# Power.net
KiCad netlist of a schematic drawn in Altium Designer
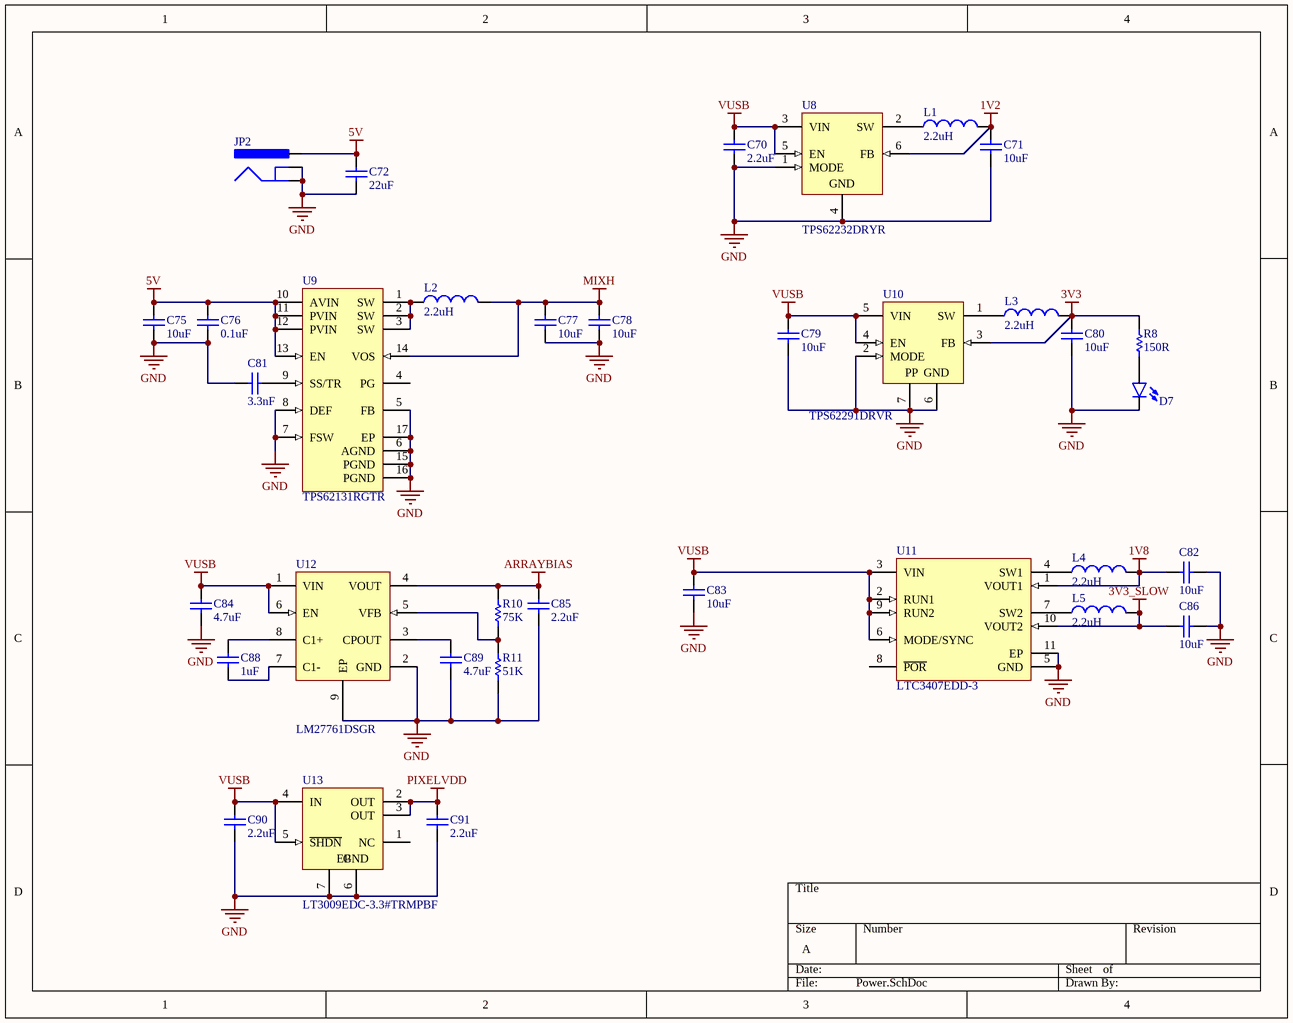
[diagram p0: Power.SchDoc]

(export (version "E")
  (design (tool "Eeschema 10.0.6"))
  (components
    (comp (ref "C70")
      (value "2.2uF")
      (footprint "C0402[1005X55]")
      (description "2.2uF 6.3V 20% 0402 (1005 Metric)")
      (fields (field (name "PARTNUMBER") "GRM155R60J225ME15D") (field (name "MANUFACTURER") "Murata"))
      (libsource (lib "Capacitors") (part "CAP_2.2uF_6.3V_0402_20%"))
    )
    (comp (ref "C71")
      (value "10uF")
      (footprint "C0402[1005X55]")
      (description "10uF 6.3V 20% 0402 (1005 Metric)")
      (fields (field (name "PARTNUMBER") "GRM155R60J106ME44D") (field (name "MANUFACTURER") "Murata"))
      (libsource (lib "Capacitors") (part "CAP_10uF_6.3V_0402_20%"))
    )
    (comp (ref "C72")
      (value "22uF")
      (footprint "C0603[1608X92]")
      (description "22uF 6.3V 10% 0603 (1608 Metric)")
      (fields (field (name "PARTNUMBER") "GRT188R60J226ME13D") (field (name "MANUFACTURER") "Murata"))
      (libsource (lib "Capacitors") (part "CAP_22uF_6.3V_0603_10%"))
    )
    (comp (ref "C75")
      (value "10uF")
      (footprint "C0402[1005X55]")
      (description "10uF 6.3V 20% 0402 (1005 Metric)")
      (fields (field (name "PARTNUMBER") "GRM155R60J106ME44D") (field (name "MANUFACTURER") "Murata"))
      (libsource (lib "Capacitors") (part "CAP_10uF_6.3V_0402_20%"))
    )
    (comp (ref "C76")
      (value "0.1uF")
      (footprint "C0402[1005X55]")
      (description "0.1uF 6.3V 10% 0402 (1005 Metric)")
      (fields (field (name "PARTNUMBER") "GRM155R70J104KA01D") (field (name "MANUFACTURER") "Murata"))
      (libsource (lib "Capacitors") (part "CAP_0.1uF_6.3V_0402_10%"))
    )
    (comp (ref "C77")
      (value "10uF")
      (footprint "C0402[1005X55]")
      (description "10uF 6.3V 20% 0402 (1005 Metric)")
      (fields (field (name "PARTNUMBER") "GRM155R60J106ME44D") (field (name "MANUFACTURER") "Murata"))
      (libsource (lib "Capacitors") (part "CAP_10uF_6.3V_0402_20%"))
    )
    (comp (ref "C78")
      (value "10uF")
      (footprint "C0402[1005X55]")
      (description "10uF 6.3V 20% 0402 (1005 Metric)")
      (fields (field (name "PARTNUMBER") "GRM155R60J106ME44D") (field (name "MANUFACTURER") "Murata"))
      (libsource (lib "Capacitors") (part "CAP_10uF_6.3V_0402_20%"))
    )
    (comp (ref "C79")
      (value "10uF")
      (footprint "C0402[1005X55]")
      (description "10uF 6.3V 20% 0402 (1005 Metric)")
      (fields (field (name "TOLERANCE") "20%") (field (name "PARTNUMBER") "GRM155R60J106ME44D"))
      (libsource (lib "Capacitors") (part "CAP_10uF_6.3V_0402_20%"))
    )
    (comp (ref "C80")
      (value "10uF")
      (footprint "C0402[1005X55]")
      (description "10uF 6.3V 20% 0402 (1005 Metric)")
      (fields (field (name "TOLERANCE") "20%") (field (name "PARTNUMBER") "GRM155R60J106ME44D"))
      (libsource (lib "Capacitors") (part "CAP_10uF_6.3V_0402_20%"))
    )
    (comp (ref "C81")
      (value "3.3nF")
      (footprint "C0402[1005X55]")
      (description "3.3nF 50V 10% 0402 (1005 Metric)")
      (fields (field (name "PARTNUMBER") "GRM155R71H332KA01D") (field (name "MANUFACTURER") "Murata"))
      (libsource (lib "Capacitors") (part "CAP_3.3nF_50V_0402_10%"))
    )
    (comp (ref "C82")
      (value "10uF")
      (footprint "C0402[1005X55]")
      (description "10uF 6.3V 20% 0402 (1005 Metric)")
      (fields (field (name "PARTNUMBER") "GRM155R60J106ME44D") (field (name "MANUFACTURER") "Murata"))
      (libsource (lib "Capacitors") (part "CAP_10uF_6.3V_0402_20%"))
    )
    (comp (ref "C83")
      (value "10uF")
      (footprint "C0402[1005X55]")
      (description "10uF 6.3V 20% 0402 (1005 Metric)")
      (fields (field (name "PARTNUMBER") "GRM155R60J106ME44D") (field (name "MANUFACTURER") "Murata"))
      (libsource (lib "Capacitors") (part "CAP_10uF_6.3V_0402_20%"))
    )
    (comp (ref "C84")
      (value "4.7uF")
      (footprint "C0402[1005X55]")
      (description "4.7uF 6.3V 20% 0402 (1005 Metric)")
      (fields (field (name "PARTNUMBER") "GRM155R60J475ME47D") (field (name "MANUFACTURER") "Murata"))
      (libsource (lib "Capacitors") (part "CAP_4.7uF_6.3V_0402_20%"))
    )
    (comp (ref "C85")
      (value "2.2uF")
      (footprint "C0402[1005X55]")
      (description "2.2uF 6.3V 20% 0402 (1005 Metric)")
      (fields (field (name "PARTNUMBER") "GRM155R60J225ME15D") (field (name "MANUFACTURER") "Murata"))
      (libsource (lib "Capacitors") (part "CAP_2.2uF_6.3V_0402_20%"))
    )
    (comp (ref "C86")
      (value "10uF")
      (footprint "C0402[1005X55]")
      (description "10uF 6.3V 20% 0402 (1005 Metric)")
      (fields (field (name "PARTNUMBER") "GRM155R60J106ME44D") (field (name "MANUFACTURER") "Murata"))
      (libsource (lib "Capacitors") (part "CAP_10uF_6.3V_0402_20%"))
    )
    (comp (ref "C88")
      (value "1uF")
      (footprint "C0402[1005X55]")
      (description "1uF 6.3V 10% 0402 (1005 Metric)")
      (fields (field (name "PARTNUMBER") "GRM155R70J105KA12D") (field (name "MANUFACTURER") "Murata"))
      (libsource (lib "Capacitors") (part "CAP_1uF_6.3V_0402_10%"))
    )
    (comp (ref "C89")
      (value "4.7uF")
      (footprint "C0402[1005X55]")
      (description "4.7uF 6.3V 20% 0402 (1005 Metric)")
      (fields (field (name "PARTNUMBER") "GRM155R60J475ME47D") (field (name "MANUFACTURER") "Murata"))
      (libsource (lib "Capacitors") (part "CAP_4.7uF_6.3V_0402_20%"))
    )
    (comp (ref "C90")
      (value "2.2uF")
      (footprint "C0402[1005X55]")
      (description "2.2uF 6.3V 20% 0402 (1005 Metric)")
      (fields (field (name "PARTNUMBER") "GRM155R60J225ME15D") (field (name "MANUFACTURER") "Murata"))
      (libsource (lib "Capacitors") (part "CAP_2.2uF_6.3V_0402_20%"))
    )
    (comp (ref "C91")
      (value "2.2uF")
      (footprint "C0402[1005X55]")
      (description "2.2uF 6.3V 20% 0402 (1005 Metric)")
      (fields (field (name "PARTNUMBER") "GRM155R60J225ME15D") (field (name "MANUFACTURER") "Murata"))
      (libsource (lib "Capacitors") (part "CAP_2.2uF_6.3V_0402_20%"))
    )
    (comp (ref "D7")
      (value "LED_0603_BLUE_5mA")
      (footprint "LED0603")
      (fields (field (name "PARTNUMBER") "LTST-C193TBKT-5A") (field (name "MANUFACTURER") "Lite-On Inc."))
      (libsource (lib "LEDs") (part "LED_0603_BLUE_5mA"))
    )
    (comp (ref "JP2")
      (value "POWER_JACK")
      (footprint "POWER-JACK-2.1X5.5MM-SMD")
      (fields (field (name "MANUFACTURER") "CUI Inc.") (field (name "PARTNUMBER") "PJ-036AH-SMT-TR"))
      (libsource (lib "Connectors") (part "POWER_JACK"))
    )
    (comp (ref "L1")
      (value "2.2uH")
      (footprint "IND0603")
      (description "2.2uH 20% 750mA 0603")
      (fields (field (name "PARTNUMBER") "LQM18PZ2R2MCHD") (field (name "MANUFACTURER") "Murata"))
      (libsource (lib "Inductors") (part "IND_2.2uH_750mA_0603_20%"))
    )
    (comp (ref "L2")
      (value "2.2uH")
      (footprint "IND1008")
      (description "2.2uH 20% 3.3A 1008")
      (fields (field (name "PARTNUMBER") "DFE252012F-2R2M=P2") (field (name "MANUFACTURER") "Murata"))
      (libsource (lib "Inductors") (part "IND_2.2uH_3.3A_1008_20%"))
    )
    (comp (ref "L3")
      (value "2.2uH")
      (footprint "IND0805")
      (description "2.2uH 20% 1.7A 0805")
      (fields (field (name "PARTNUMBER") "LQM21PN2R2MGHL") (field (name "MANUFACTURER") "Murata"))
      (libsource (lib "Inductors") (part "IND_2.2uH_1.7A_0805_20%"))
    )
    (comp (ref "L4")
      (value "2.2uH")
      (footprint "IND0603")
      (description "2.2uH 20% 750mA 0603")
      (fields (field (name "PARTNUMBER") "LQM18PZ2R2MCHD") (field (name "MANUFACTURER") "Murata"))
      (libsource (lib "Inductors") (part "IND_2.2uH_750mA_0603_20%"))
    )
    (comp (ref "L5")
      (value "2.2uH")
      (footprint "IND0603")
      (description "2.2uH 20% 750mA 0603")
      (fields (field (name "PARTNUMBER") "LQM18PZ2R2MCHD") (field (name "MANUFACTURER") "Murata"))
      (libsource (lib "Inductors") (part "IND_2.2uH_750mA_0603_20%"))
    )
    (comp (ref "R8")
      (value "150R")
      (footprint "R0402[1005]")
      (description "150R 0.063W 1% 0402 (1005 Metric)")
      (fields (field (name "MANUFACTURER") "KOA Speer") (field (name "PARTNUMBER") "RK73H1ETTP1500F"))
      (libsource (lib "Resistors") (part "RES_150R_0402_1%"))
    )
    (comp (ref "R10")
      (value "75K")
      (footprint "R0402[1005]")
      (description "75K 0.063W 1% 0402 (1005 Metric)")
      (fields (field (name "MANUFACTURER") "KOA Speer") (field (name "PARTNUMBER") "RK73H1ETTP7502F"))
      (libsource (lib "Resistors") (part "RES_75K_0402_1%"))
    )
    (comp (ref "R11")
      (value "51K")
      (footprint "R0402[1005]")
      (description "51K 0.063W 1% 0402 (1005 Metric)")
      (fields (field (name "MANUFACTURER") "KOA Speer") (field (name "PARTNUMBER") "RK73H1ETTP5102F"))
      (libsource (lib "Resistors") (part "RES_51K_0402_1%"))
    )
    (comp (ref "U8")
      (value "TPS62232DRYR")
      (footprint "DRY0006A")
      (fields (field (name "MANUFACTURER") "Texas Instruments"))
      (libsource (lib "Altium Content Vault") (part "TI-TPS62232DRY6"))
    )
    (comp (ref "U9")
      (value "TPS62131RGTR")
      (footprint "RGT0016C_V")
      (fields (field (name "MANUFACTURER") "Texas Instruments"))
      (libsource (lib "Altium Content Vault") (part "TI-TPS62131RGT16-1700X1700TP"))
    )
    (comp (ref "U10")
      (value "TPS62291DRVR")
      (footprint "WSON-6")
      (description "Voltage Regulators - Switching Regulators 2.25MHz 1A Step-Down Cnvrtr 3.3V Output")
      (fields (field (name "MANUFACTURER") "Texas Instruments"))
      (libsource (lib "ICs") (part "TPS62291DRVR"))
    )
    (comp (ref "U11")
      (value "LTC3407EDD-3")
      (footprint "VSON-10 (3mmx3mm)")
      (fields (field (name "MANUFACTURER") "Linear Technology"))
      (libsource (lib "ICs") (part "LTC3407EDD-3"))
    )
    (comp (ref "U12")
      (value "LM27761DSGR")
      (footprint "WSON-8")
      (description "Switching Voltage Regulators Switch Cap Boost")
      (fields (field (name "MANUFACTURER") "Texas Instruments"))
      (libsource (lib "ICs") (part "LM27761DSGR"))
    )
    (comp (ref "U13")
      (value "LT3009EDC-3.3#TRMPBF")
      (footprint "LT-DC6-6_V")
      (fields (field (name "MANUFACTURER") "Linear Technology"))
      (libsource (lib "Altium Content Vault") (part "LT-LT3009-DC6-6"))
    )
  )
  (nets
    (net (code "1") (name "1V2") (class "Default")
      (node (ref "C71") (pin "2") (pinfunction "2_2") (pintype "passive"))
      (node (ref "L1") (pin "2") (pinfunction "2_2") (pintype "passive"))
      (node (ref "U8") (pin "6") (pinfunction "FB_6") (pintype "input"))
    )
    (net (code "2") (name "1V8") (class "Default")
      (node (ref "C82") (pin "2") (pinfunction "2_2") (pintype "passive"))
      (node (ref "L4") (pin "2") (pinfunction "2_2") (pintype "passive"))
      (node (ref "U11") (pin "1") (pinfunction "VOUT1_1") (pintype "input"))
    )
    (net (code "3") (name "3V3") (class "Default")
      (node (ref "C80") (pin "2") (pinfunction "2_2") (pintype "passive"))
      (node (ref "L3") (pin "2") (pinfunction "2_2") (pintype "passive"))
      (node (ref "R8") (pin "2") (pinfunction "2_2") (pintype "passive"))
      (node (ref "U10") (pin "3") (pinfunction "FB_3") (pintype "input"))
    )
    (net (code "4") (name "3V3_SLOW") (class "Default")
      (node (ref "C86") (pin "1") (pinfunction "1_1") (pintype "passive"))
      (node (ref "L5") (pin "2") (pinfunction "2_2") (pintype "passive"))
      (node (ref "U11") (pin "10") (pinfunction "VOUT2_10") (pintype "input"))
    )
    (net (code "5") (name "5V") (class "Default")
      (node (ref "C72") (pin "2") (pinfunction "2_2") (pintype "passive"))
      (node (ref "C75") (pin "2") (pinfunction "2_2") (pintype "passive"))
      (node (ref "C76") (pin "2") (pinfunction "2_2") (pintype "passive"))
      (node (ref "JP2") (pin "1") (pinfunction "PWR_1") (pintype "passive"))
      (node (ref "U9") (pin "10") (pinfunction "AVIN_10") (pintype "power_in"))
      (node (ref "U9") (pin "11") (pinfunction "PVIN_11") (pintype "power_in"))
      (node (ref "U9") (pin "12") (pinfunction "PVIN_12") (pintype "power_in"))
      (node (ref "U9") (pin "13") (pinfunction "EN_13") (pintype "input"))
    )
    (net (code "6") (name "ARRAYBIAS") (class "Default")
      (node (ref "C85") (pin "2") (pinfunction "2_2") (pintype "passive"))
      (node (ref "R10") (pin "2") (pinfunction "2_2") (pintype "passive"))
      (node (ref "U12") (pin "4") (pinfunction "VOUT_4") (pintype "power_in"))
    )
    (net (code "7") (name "GND") (class "Default")
      (node (ref "C70") (pin "1") (pinfunction "1_1") (pintype "passive"))
      (node (ref "C71") (pin "1") (pinfunction "1_1") (pintype "passive"))
      (node (ref "C72") (pin "1") (pinfunction "1_1") (pintype "passive"))
      (node (ref "C75") (pin "1") (pinfunction "1_1") (pintype "passive"))
      (node (ref "C76") (pin "1") (pinfunction "1_1") (pintype "passive"))
      (node (ref "C77") (pin "1") (pinfunction "1_1") (pintype "passive"))
      (node (ref "C78") (pin "1") (pinfunction "1_1") (pintype "passive"))
      (node (ref "C79") (pin "1") (pinfunction "1_1") (pintype "passive"))
      (node (ref "C80") (pin "1") (pinfunction "1_1") (pintype "passive"))
      (node (ref "C81") (pin "1") (pinfunction "1_1") (pintype "passive"))
      (node (ref "C82") (pin "1") (pinfunction "1_1") (pintype "passive"))
      (node (ref "C83") (pin "1") (pinfunction "1_1") (pintype "passive"))
      (node (ref "C84") (pin "1") (pinfunction "1_1") (pintype "passive"))
      (node (ref "C85") (pin "1") (pinfunction "1_1") (pintype "passive"))
      (node (ref "C86") (pin "2") (pinfunction "2_2") (pintype "passive"))
      (node (ref "C89") (pin "1") (pinfunction "1_1") (pintype "passive"))
      (node (ref "C90") (pin "1") (pinfunction "1_1") (pintype "passive"))
      (node (ref "C91") (pin "1") (pinfunction "1_1") (pintype "passive"))
      (node (ref "D7") (pin "C") (pinfunction "C_C") (pintype "passive"))
      (node (ref "JP2") (pin "2") (pinfunction "GND_2") (pintype "passive"))
      (node (ref "JP2") (pin "3") (pinfunction "GND_3") (pintype "passive"))
      (node (ref "R11") (pin "1") (pinfunction "1_1") (pintype "passive"))
      (node (ref "U10") (pin "2") (pinfunction "MODE_2") (pintype "input"))
      (node (ref "U10") (pin "6") (pinfunction "GND_6") (pintype "power_in"))
      (node (ref "U10") (pin "7") (pinfunction "EP_7") (pintype "passive"))
      (node (ref "U11") (pin "11") (pinfunction "EP_11") (pintype "power_in"))
      (node (ref "U11") (pin "5") (pinfunction "GND_5") (pintype "power_in"))
      (node (ref "U12") (pin "2") (pinfunction "GND_2") (pintype "power_in"))
      (node (ref "U12") (pin "9") (pinfunction "EP_9") (pintype "passive"))
      (node (ref "U13") (pin "6") (pinfunction "GND_6") (pintype "power_in"))
      (node (ref "U13") (pin "7") (pinfunction "EP_7") (pintype "power_in"))
      (node (ref "U8") (pin "1") (pinfunction "MODE_1") (pintype "input"))
      (node (ref "U8") (pin "4") (pinfunction "GND_4") (pintype "power_in"))
      (node (ref "U9") (pin "15") (pinfunction "PGND_15") (pintype "power_in"))
      (node (ref "U9") (pin "16") (pinfunction "PGND_16") (pintype "power_in"))
      (node (ref "U9") (pin "17") (pinfunction "EP_17") (pintype "power_in"))
      (node (ref "U9") (pin "5") (pinfunction "FB_5") (pintype "passive"))
      (node (ref "U9") (pin "6") (pinfunction "AGND_6") (pintype "power_in"))
      (node (ref "U9") (pin "7") (pinfunction "FSW_7") (pintype "input"))
      (node (ref "U9") (pin "8") (pinfunction "DEF_8") (pintype "input"))
    )
    (net (code "8") (name "MIXH") (class "Default")
      (node (ref "C77") (pin "2") (pinfunction "2_2") (pintype "passive"))
      (node (ref "C78") (pin "2") (pinfunction "2_2") (pintype "passive"))
      (node (ref "L2") (pin "2") (pinfunction "2_2") (pintype "passive"))
      (node (ref "U9") (pin "14") (pinfunction "VOS_14") (pintype "input"))
    )
    (net (code "9") (name "Net-(D7-PadA)") (class "Default")
      (node (ref "D7") (pin "A") (pinfunction "A_A") (pintype "passive"))
      (node (ref "R8") (pin "1") (pinfunction "1_1") (pintype "passive"))
    )
    (net (code "10") (name "Net-(L2-Pad1)") (class "Default")
      (node (ref "L2") (pin "1") (pinfunction "1_1") (pintype "passive"))
      (node (ref "U9") (pin "1") (pinfunction "SW_1") (pintype "power_in"))
      (node (ref "U9") (pin "2") (pinfunction "SW_2") (pintype "power_in"))
      (node (ref "U9") (pin "3") (pinfunction "SW_3") (pintype "power_in"))
    )
    (net (code "11") (name "Net-(U8-SW)") (class "Default")
      (node (ref "L1") (pin "1") (pinfunction "1_1") (pintype "passive"))
      (node (ref "U8") (pin "2") (pinfunction "SW_2") (pintype "power_in"))
    )
    (net (code "12") (name "Net-(U9-SS{slash}TR)") (class "Default")
      (node (ref "C81") (pin "2") (pinfunction "2_2") (pintype "passive"))
      (node (ref "U9") (pin "9") (pinfunction "SS/TR_9") (pintype "input"))
    )
    (net (code "13") (name "Net-(U10-SW)") (class "Default")
      (node (ref "L3") (pin "1") (pinfunction "1_1") (pintype "passive"))
      (node (ref "U10") (pin "1") (pinfunction "SW_1") (pintype "power_in"))
    )
    (net (code "14") (name "Net-(U11-SW1)") (class "Default")
      (node (ref "L4") (pin "1") (pinfunction "1_1") (pintype "passive"))
      (node (ref "U11") (pin "4") (pinfunction "SW1_4") (pintype "power_in"))
    )
    (net (code "15") (name "Net-(U11-SW2)") (class "Default")
      (node (ref "L5") (pin "1") (pinfunction "1_1") (pintype "passive"))
      (node (ref "U11") (pin "7") (pinfunction "SW2_7") (pintype "power_in"))
    )
    (net (code "16") (name "Net-(U12-C1+)") (class "Default")
      (node (ref "C88") (pin "2") (pinfunction "2_2") (pintype "passive"))
      (node (ref "U12") (pin "8") (pinfunction "C1+_8") (pintype "power_in"))
    )
    (net (code "17") (name "Net-(U12-C1-)") (class "Default")
      (node (ref "C88") (pin "1") (pinfunction "1_1") (pintype "passive"))
      (node (ref "U12") (pin "7") (pinfunction "C1-_7") (pintype "power_in"))
    )
    (net (code "18") (name "Net-(U12-CPOUT)") (class "Default")
      (node (ref "C89") (pin "2") (pinfunction "2_2") (pintype "passive"))
      (node (ref "U12") (pin "3") (pinfunction "CPOUT_3") (pintype "power_in"))
    )
    (net (code "19") (name "Net-(U12-VFB)") (class "Default")
      (node (ref "R10") (pin "1") (pinfunction "1_1") (pintype "passive"))
      (node (ref "R11") (pin "2") (pinfunction "2_2") (pintype "passive"))
      (node (ref "U12") (pin "5") (pinfunction "VFB_5") (pintype "input"))
    )
    (net (code "20") (name "PIXELVDD") (class "Default")
      (node (ref "C91") (pin "2") (pinfunction "2_2") (pintype "passive"))
      (node (ref "U13") (pin "2") (pinfunction "OUT_2") (pintype "power_in"))
      (node (ref "U13") (pin "3") (pinfunction "OUT_3") (pintype "power_in"))
    )
    (net (code "21") (name "VUSB") (class "Default")
      (node (ref "C70") (pin "2") (pinfunction "2_2") (pintype "passive"))
      (node (ref "C79") (pin "2") (pinfunction "2_2") (pintype "passive"))
      (node (ref "C83") (pin "2") (pinfunction "2_2") (pintype "passive"))
      (node (ref "C84") (pin "2") (pinfunction "2_2") (pintype "passive"))
      (node (ref "C90") (pin "2") (pinfunction "2_2") (pintype "passive"))
      (node (ref "U10") (pin "4") (pinfunction "EN_4") (pintype "input"))
      (node (ref "U10") (pin "5") (pinfunction "VIN_5") (pintype "power_in"))
      (node (ref "U11") (pin "2") (pinfunction "RUN1_2") (pintype "input"))
      (node (ref "U11") (pin "3") (pinfunction "VIN_3") (pintype "power_in"))
      (node (ref "U11") (pin "6") (pinfunction "MODE/SYNC_6") (pintype "input"))
      (node (ref "U11") (pin "9") (pinfunction "RUN2_9") (pintype "input"))
      (node (ref "U12") (pin "1") (pinfunction "VIN_1") (pintype "power_in"))
      (node (ref "U12") (pin "6") (pinfunction "EN_6") (pintype "input"))
      (node (ref "U13") (pin "4") (pinfunction "IN_4") (pintype "power_in"))
      (node (ref "U13") (pin "5") (pinfunction "~{SHDN}_5") (pintype "input"))
      (node (ref "U8") (pin "3") (pinfunction "VIN_3") (pintype "power_in"))
      (node (ref "U8") (pin "5") (pinfunction "EN_5") (pintype "input"))
    )
    (net (code "22") (name "unconnected-(U9-PG-Pad4)") (class "Default")
      (node (ref "U9") (pin "4") (pinfunction "PG_4") (pintype "tri_state"))
    )
    (net (code "23") (name "unconnected-(U11-~{POR}-Pad8)") (class "Default")
      (node (ref "U11") (pin "8") (pinfunction "~{POR}_8") (pintype "open_collector"))
    )
    (net (code "24") (name "unconnected-(U13-NC-Pad1)") (class "Default")
      (node (ref "U13") (pin "1") (pinfunction "NC_1") (pintype "passive"))
    )
  )
)
